# SCH_USB-Hub-with-audio-card_2025-04-09.net
KiCad netlist of a schematic drawn in EasyEDA
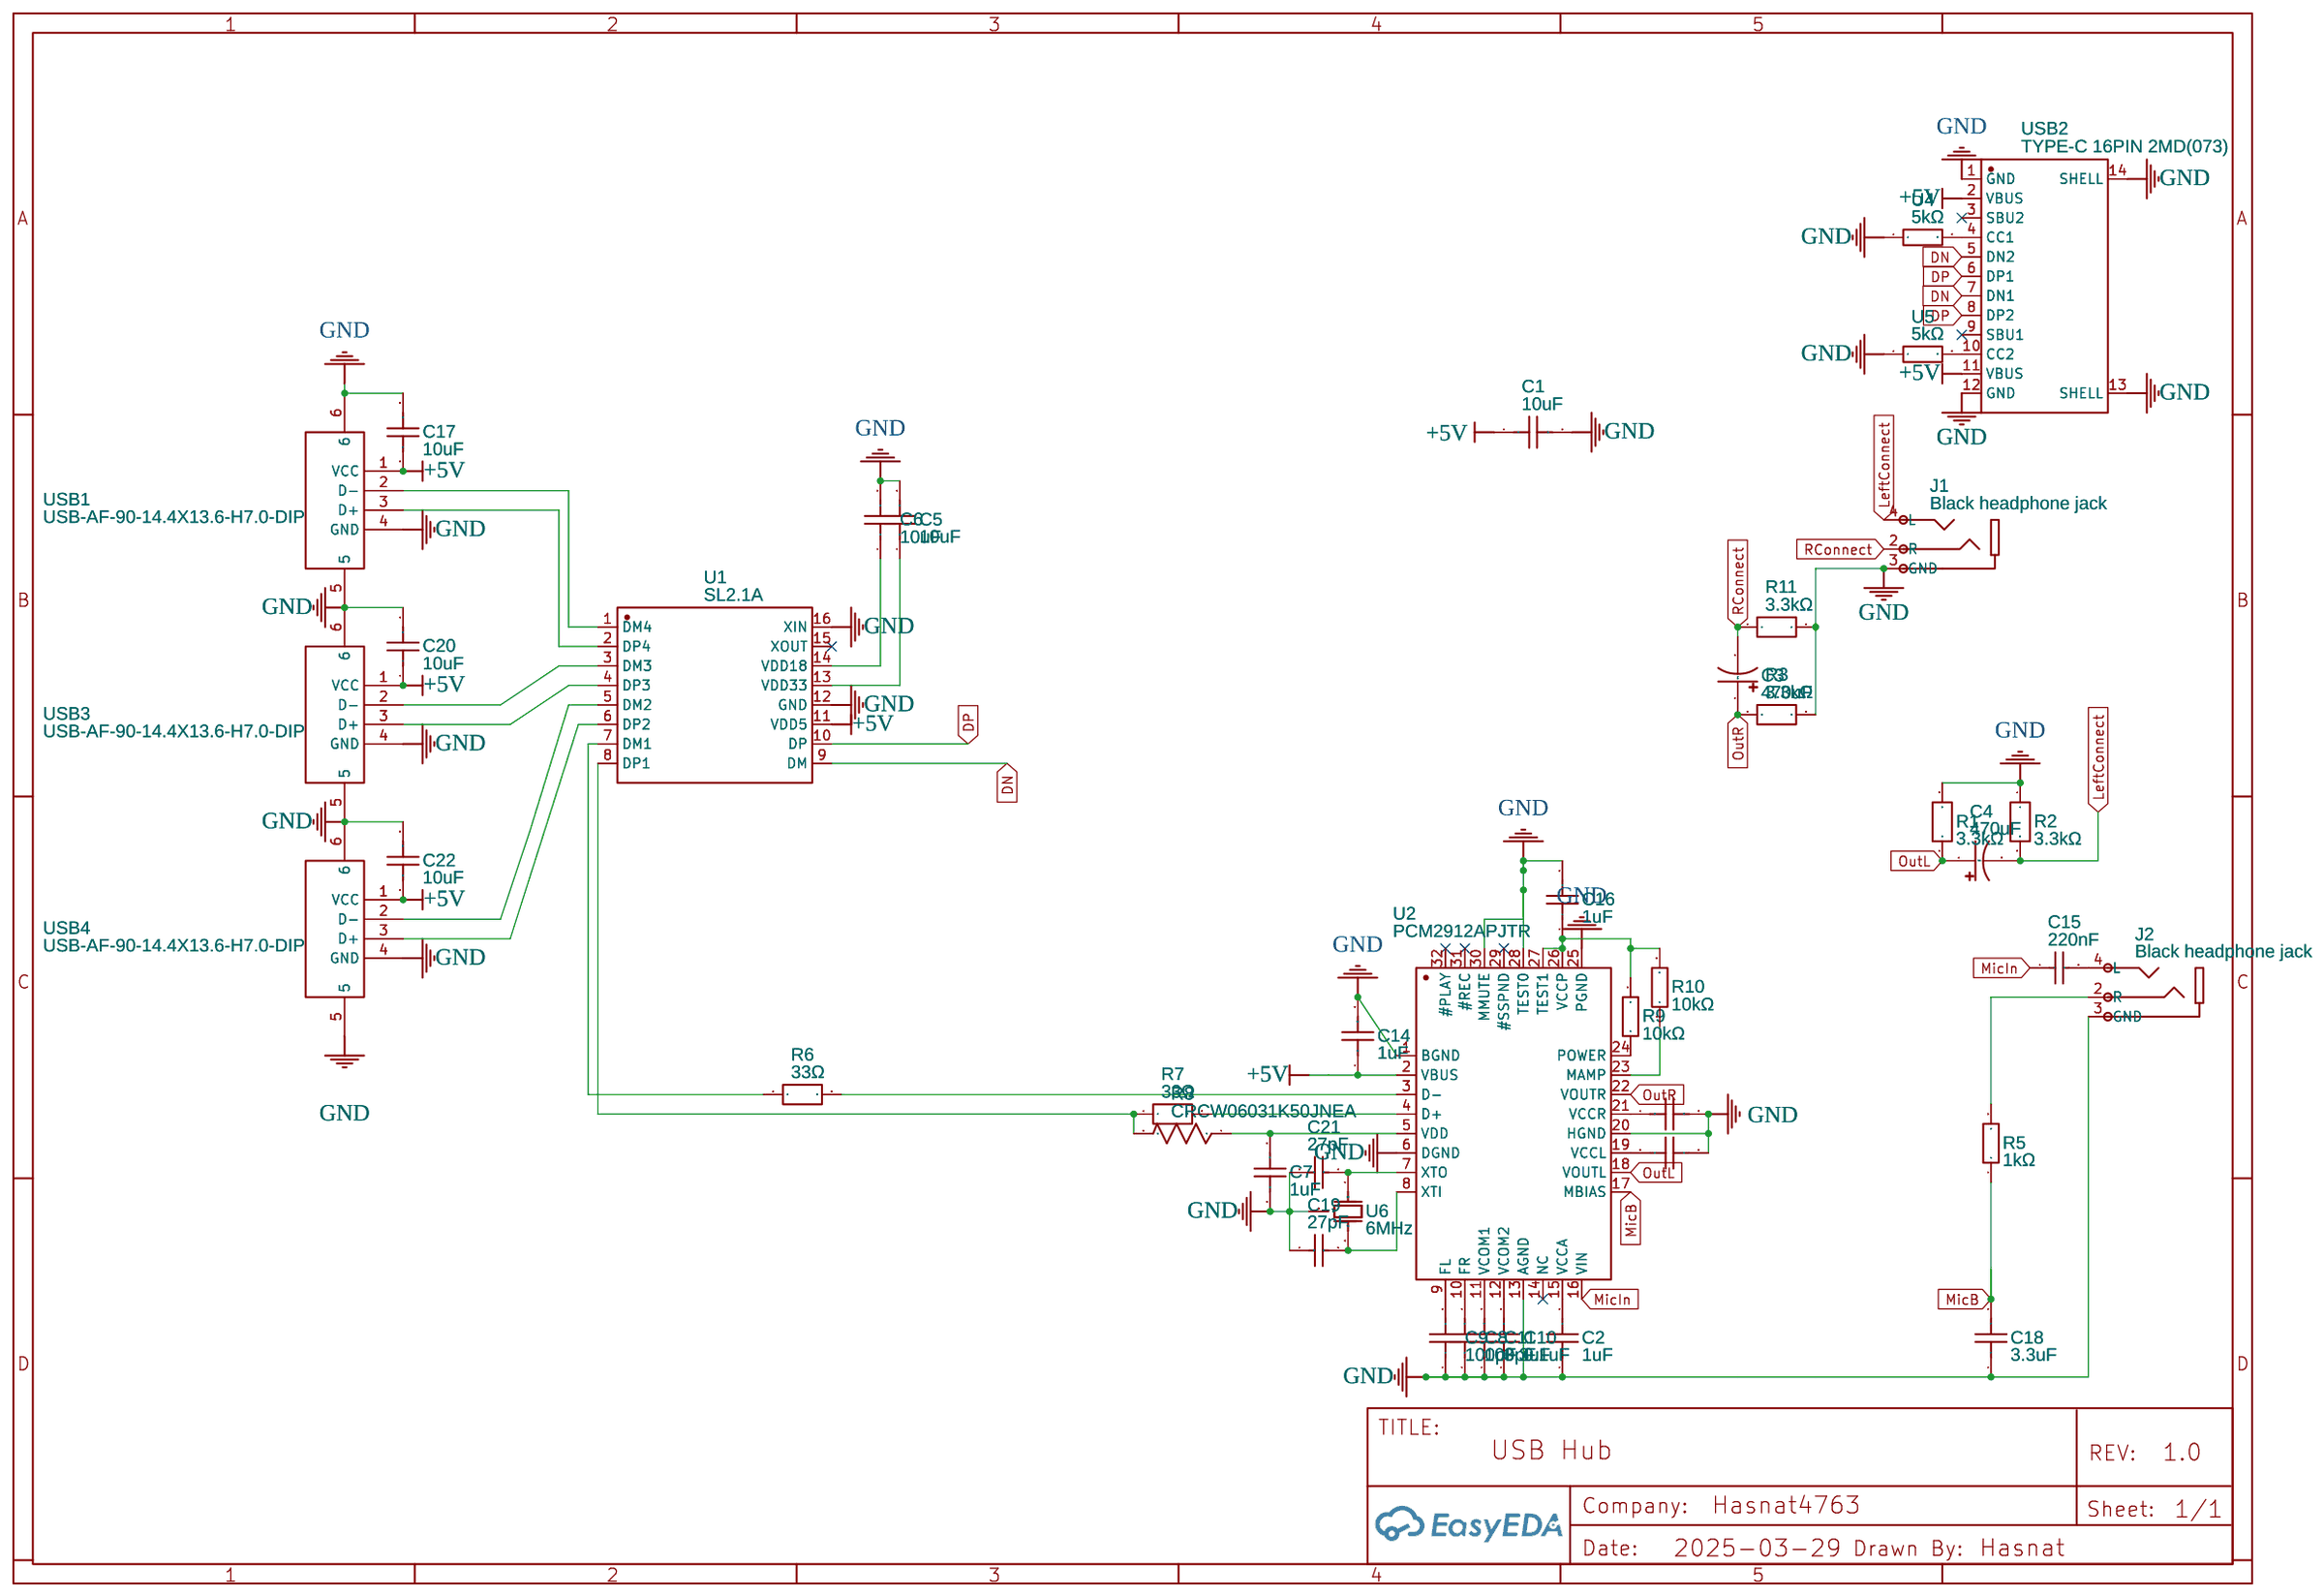
[diagram p0: schematic sheet]

(export (version "E")
  (design (tool "Eeschema 10.0.6"))
  (components
    (comp (ref "C1")
      (value "10uF")
      (fields
        (field (name "Manufacturer Part") "CL10A106KP8NNNC")
        (field (name "Manufacturer") "SAMSUNG(三星)")
      )
      (libsource (lib "") (part "CL10A106KP8NNNC_1"))
    )
    (comp (ref "C2")
      (value "1uF")
      (fields (field (name "Manufacturer Part") "CGB3B1X7R1A105K055AC") (field (name "Manufacturer") "TDK"))
      (libsource (lib "") (part "CGB3B1X7R1A105K055AC"))
    )
    (comp (ref "C3")
      (value "470uF")
      (fields (field (name "Manufacturer Part") "UKW1C471MPD") (field (name "Manufacturer") "Nichicon(尼吉康)"))
      (libsource (lib "") (part "UKW1C471MPD_1"))
    )
    (comp (ref "C4")
      (value "470uF")
      (fields (field (name "Manufacturer Part") "UKW1C471MPD") (field (name "Manufacturer") "Nichicon(尼吉康)"))
      (libsource (lib "") (part "UKW1C471MPD"))
    )
    (comp (ref "C5")
      (value "10uF")
      (fields
        (field (name "Manufacturer Part") "CL10A106KP8NNNC")
        (field (name "Manufacturer") "SAMSUNG(三星)")
      )
      (libsource (lib "") (part "CL10A106KP8NNNC"))
    )
    (comp (ref "C6")
      (value "10uF")
      (fields
        (field (name "Manufacturer Part") "CL10A106KP8NNNC")
        (field (name "Manufacturer") "SAMSUNG(三星)")
      )
      (libsource (lib "") (part "CL10A106KP8NNNC"))
    )
    (comp (ref "C7")
      (value "1uF")
      (fields
        (field (name "Manufacturer Part") "CL31B105KBHNNNE")
        (field (name "Manufacturer") "SAMSUNG(三星)")
      )
      (libsource (lib "") (part "CL31B105KBHNNNE_1"))
    )
    (comp (ref "C8")
      (value "100pF")
      (fields
        (field (name "Manufacturer Part") "CL10A106KP8NNNC")
        (field (name "Manufacturer") "SAMSUNG(三星)")
      )
      (libsource (lib "") (part "CL10A106KP8NNNC"))
    )
    (comp (ref "C9")
      (value "100pF")
      (fields
        (field (name "Manufacturer Part") "CL10A106KP8NNNC")
        (field (name "Manufacturer") "SAMSUNG(三星)")
      )
      (libsource (lib "") (part "CL10A106KP8NNNC"))
    )
    (comp (ref "C10")
      (value "0.1uF")
      (fields
        (field (name "Manufacturer Part") "CL10A106KP8NNNC")
        (field (name "Manufacturer") "SAMSUNG(三星)")
      )
      (libsource (lib "") (part "CL10A106KP8NNNC"))
    )
    (comp (ref "C11")
      (value "3.3uF")
      (fields
        (field (name "Manufacturer Part") "CL10A106KP8NNNC")
        (field (name "Manufacturer") "SAMSUNG(三星)")
      )
      (libsource (lib "") (part "CL10A106KP8NNNC"))
    )
    (comp (ref "C12")
      (value "1uF")
      (fields
        (field (name "Manufacturer Part") "CL31B105KBHNNNE")
        (field (name "Manufacturer") "SAMSUNG(三星)")
      )
      (libsource (lib "") (part "CL31B105KBHNNNE"))
    )
    (comp (ref "C13")
      (value "1uF")
      (fields
        (field (name "Manufacturer Part") "CL31B105KBHNNNE")
        (field (name "Manufacturer") "SAMSUNG(三星)")
      )
      (libsource (lib "") (part "CL31B105KBHNNNE"))
    )
    (comp (ref "C14")
      (value "1uF")
      (fields (field (name "Manufacturer Part") "CGB3B1X7R1A105K055AC") (field (name "Manufacturer") "TDK"))
      (libsource (lib "") (part "CGB3B1X7R1A105K055AC"))
    )
    (comp (ref "C15")
      (value "220nF")
      (fields
        (field (name "Manufacturer Part") "CL05A224KA5NNNC")
        (field (name "Manufacturer") "SAMSUNG(三星)")
      )
      (libsource (lib "") (part "CL05A224KA5NNNC"))
    )
    (comp (ref "C16")
      (value "1uF")
      (fields
        (field (name "Manufacturer Part") "CL31B105KBHNNNE")
        (field (name "Manufacturer") "SAMSUNG(三星)")
      )
      (libsource (lib "") (part "CL31B105KBHNNNE_1"))
    )
    (comp (ref "C17")
      (value "10uF")
      (fields
        (field (name "Manufacturer Part") "CL10A106KP8NNNC")
        (field (name "Manufacturer") "SAMSUNG(三星)")
      )
      (libsource (lib "") (part "CL10A106KP8NNNC"))
    )
    (comp (ref "C18")
      (value "3.3uF")
      (fields
        (field (name "Manufacturer Part") "KVD500L335M55A0T00")
        (field (name "Manufacturer") "NCC(日本贵弥功)")
      )
      (libsource (lib "") (part "KVD500L335M55A0T00"))
    )
    (comp (ref "C19")
      (value "27pF")
      (fields
        (field (name "Manufacturer Part") "CC0805JRNPO9BN270")
        (field (name "Manufacturer") "YAGEO(国巨)")
      )
      (libsource (lib "") (part "CC0805JRNPO9BN270"))
    )
    (comp (ref "C20")
      (value "10uF")
      (fields
        (field (name "Manufacturer Part") "CL10A106KP8NNNC")
        (field (name "Manufacturer") "SAMSUNG(三星)")
      )
      (libsource (lib "") (part "CL10A106KP8NNNC"))
    )
    (comp (ref "C21")
      (value "27pF")
      (fields
        (field (name "Manufacturer Part") "CC0805JRNPO9BN270")
        (field (name "Manufacturer") "YAGEO(国巨)")
      )
      (libsource (lib "") (part "CC0805JRNPO9BN270"))
    )
    (comp (ref "C22")
      (value "10uF")
      (fields
        (field (name "Manufacturer Part") "CL10A106KP8NNNC")
        (field (name "Manufacturer") "SAMSUNG(三星)")
      )
      (libsource (lib "") (part "CL10A106KP8NNNC"))
    )
    (comp (ref "J1")
      (value "Black headphone jack")
      (fields (field (name "Manufacturer Part") "320B直插") (field (name "Manufacturer") "BOOMELE(博穆精密)"))
      (libsource (lib "") (part "Black headphone jack"))
    )
    (comp (ref "J2")
      (value "Black headphone jack")
      (fields (field (name "Manufacturer Part") "320B直插") (field (name "Manufacturer") "BOOMELE(博穆精密)"))
      (libsource (lib "") (part "Black headphone jack"))
    )
    (comp (ref "R1")
      (value "3.3kΩ")
      (fields (field (name "Manufacturer Part") "CR-05JL7---3K3") (field (name "Manufacturer") "Viking(光颉)"))
      (libsource (lib "") (part "CR-05JL7---3K3_2"))
    )
    (comp (ref "R2")
      (value "3.3kΩ")
      (fields (field (name "Manufacturer Part") "CR-05JL7---3K3") (field (name "Manufacturer") "Viking(光颉)"))
      (libsource (lib "") (part "CR-05JL7---3K3"))
    )
    (comp (ref "R3")
      (value "3.3kΩ")
      (fields (field (name "Manufacturer Part") "CR-05JL7---3K3") (field (name "Manufacturer") "Viking(光颉)"))
      (libsource (lib "") (part "CR-05JL7---3K3_1"))
    )
    (comp (ref "R5")
      (value "1kΩ")
      (fields (field (name "Manufacturer Part") "RT0603DRD071KL") (field (name "Manufacturer") "YAGEO(国巨)"))
      (libsource (lib "") (part "RT0603DRD071KL"))
    )
    (comp (ref "R6")
      (value "33Ω")
      (fields
        (field (name "Manufacturer Part") "CRCW060333R0JNEA")
        (field (name "Manufacturer") "VISHAY(威世)")
      )
      (libsource (lib "") (part "CRCW060333R0JNEA"))
    )
    (comp (ref "R7")
      (value "33Ω")
      (fields
        (field (name "Manufacturer Part") "CRCW060333R0JNEA")
        (field (name "Manufacturer") "VISHAY(威世)")
      )
      (libsource (lib "") (part "CRCW060333R0JNEA"))
    )
    (comp (ref "R8") (value "CRCW06031K50JNEA") (libsource (lib "") (part "CRCW06031K50JNEA")))
    (comp (ref "R9")
      (value "10kΩ")
      (fields
        (field (name "Manufacturer Part") "CRCW060310K0JNEA")
        (field (name "Manufacturer") "VISHAY(威世)")
      )
      (libsource (lib "") (part "CRCW060310K0JNEA"))
    )
    (comp (ref "R10")
      (value "10kΩ")
      (fields
        (field (name "Manufacturer Part") "CRCW060310K0JNEA")
        (field (name "Manufacturer") "VISHAY(威世)")
      )
      (libsource (lib "") (part "CRCW060310K0JNEA"))
    )
    (comp (ref "R11")
      (value "3.3kΩ")
      (fields (field (name "Manufacturer Part") "CR-05JL7---3K3") (field (name "Manufacturer") "Viking(光颉)"))
      (libsource (lib "") (part "CR-05JL7---3K3_1"))
    )
    (comp (ref "U1")
      (value "SL2.1A")
      (fields (field (name "Manufacturer") "CoreChips(和芯润德)"))
      (libsource (lib "") (part "SL2.1A"))
    )
    (comp (ref "U2")
      (value "PCM2912APJTR")
      (fields (field (name "Manufacturer") "TI(德州仪器)"))
      (libsource (lib "") (part "PCM2912APJTR"))
    )
    (comp (ref "U4")
      (value "5kΩ")
      (fields (field (name "Manufacturer Part") "MFP1WSBRD52-5K") (field (name "Manufacturer") "YAGEO(国巨)"))
      (libsource (lib "") (part "MFP1WSBRD52-5K"))
    )
    (comp (ref "U5")
      (value "5kΩ")
      (fields (field (name "Manufacturer Part") "MFP1WSBRD52-5K") (field (name "Manufacturer") "YAGEO(国巨)"))
      (libsource (lib "") (part "MFP1WSBRD52-5K"))
    )
    (comp (ref "U6")
      (value "6MHz")
      (fields (field (name "Manufacturer Part") "ECS-60-18-5G3X-JGN-TR") (field (name "Manufacturer") "ECS"))
      (libsource (lib "") (part "ECS-60-18-5G3X-JGN-TR"))
    )
    (comp (ref "USB1")
      (value "USB-AF-90-14.4X13.6-H7.0-DIP")
      (fields (field (name "Manufacturer Part") "903-131A1011D10100") (field (name "Manufacturer") "精拓金"))
      (libsource (lib "") (part "USB-AF-90-14.4X13.6-H7.0-DIP"))
    )
    (comp (ref "USB2")
      (value "TYPE-C 16PIN 2MD(073)")
      (fields (field (name "Manufacturer") "SHOU HAN(首韩)"))
      (libsource (lib "") (part "TYPE-C 16PIN 2MD(073)"))
    )
    (comp (ref "USB3")
      (value "USB-AF-90-14.4X13.6-H7.0-DIP")
      (fields (field (name "Manufacturer Part") "903-131A1011D10100") (field (name "Manufacturer") "精拓金"))
      (libsource (lib "") (part "USB-AF-90-14.4X13.6-H7.0-DIP"))
    )
    (comp (ref "USB4")
      (value "USB-AF-90-14.4X13.6-H7.0-DIP")
      (fields (field (name "Manufacturer Part") "903-131A1011D10100") (field (name "Manufacturer") "精拓金"))
      (libsource (lib "") (part "USB-AF-90-14.4X13.6-H7.0-DIP"))
    )
  )
  (nets
    (net (code "1") (name "+5V") (class "Default")
      (node (ref "C1") (pin "1") (pinfunction "1_1") (pintype "unspecified"))
      (node (ref "C14") (pin "1") (pinfunction "1_1") (pintype "unspecified"))
      (node (ref "C17") (pin "1") (pinfunction "1_1") (pintype "unspecified"))
      (node (ref "C20") (pin "1") (pinfunction "1_1") (pintype "unspecified"))
      (node (ref "C22") (pin "1") (pinfunction "1_1") (pintype "unspecified"))
      (node (ref "U1") (pin "11") (pinfunction "VDD5_11") (pintype "unspecified"))
      (node (ref "U2") (pin "2") (pinfunction "VBUS_2") (pintype "unspecified"))
      (node (ref "USB1") (pin "1") (pinfunction "VCC_1") (pintype "unspecified"))
      (node (ref "USB2") (pin "11") (pinfunction "VBUS_11") (pintype "unspecified"))
      (node (ref "USB2") (pin "2") (pinfunction "VBUS_2") (pintype "unspecified"))
      (node (ref "USB3") (pin "1") (pinfunction "VCC_1") (pintype "unspecified"))
      (node (ref "USB4") (pin "1") (pinfunction "VCC_1") (pintype "unspecified"))
    )
    (net (code "2") (name "DN") (class "Default")
      (node (ref "U1") (pin "9") (pinfunction "DM_9") (pintype "unspecified"))
      (node (ref "USB2") (pin "5") (pinfunction "DN2_5") (pintype "unspecified"))
      (node (ref "USB2") (pin "7") (pinfunction "DN1_7") (pintype "unspecified"))
    )
    (net (code "3") (name "DP") (class "Default")
      (node (ref "U1") (pin "10") (pinfunction "DP_10") (pintype "unspecified"))
      (node (ref "USB2") (pin "6") (pinfunction "DP1_6") (pintype "unspecified"))
      (node (ref "USB2") (pin "8") (pinfunction "DP2_8") (pintype "unspecified"))
    )
    (net (code "4") (name "GND") (class "Default")
      (node (ref "C1") (pin "2") (pinfunction "2_2") (pintype "unspecified"))
      (node (ref "C10") (pin "1") (pinfunction "1_1") (pintype "unspecified"))
      (node (ref "C11") (pin "1") (pinfunction "1_1") (pintype "unspecified"))
      (node (ref "C12") (pin "2") (pinfunction "2_2") (pintype "unspecified"))
      (node (ref "C13") (pin "2") (pinfunction "2_2") (pintype "unspecified"))
      (node (ref "C14") (pin "2") (pinfunction "2_2") (pintype "unspecified"))
      (node (ref "C16") (pin "2") (pinfunction "2_2") (pintype "unspecified"))
      (node (ref "C17") (pin "2") (pinfunction "2_2") (pintype "unspecified"))
      (node (ref "C18") (pin "1") (pinfunction "1_1") (pintype "unspecified"))
      (node (ref "C19") (pin "1") (pinfunction "1_1") (pintype "input"))
      (node (ref "C2") (pin "1") (pinfunction "1_1") (pintype "unspecified"))
      (node (ref "C20") (pin "2") (pinfunction "2_2") (pintype "unspecified"))
      (node (ref "C21") (pin "1") (pinfunction "1_1") (pintype "input"))
      (node (ref "C22") (pin "2") (pinfunction "2_2") (pintype "unspecified"))
      (node (ref "C5") (pin "2") (pinfunction "2_2") (pintype "unspecified"))
      (node (ref "C6") (pin "2") (pinfunction "2_2") (pintype "unspecified"))
      (node (ref "C7") (pin "1") (pinfunction "1_1") (pintype "unspecified"))
      (node (ref "C8") (pin "1") (pinfunction "1_1") (pintype "unspecified"))
      (node (ref "C9") (pin "1") (pinfunction "1_1") (pintype "unspecified"))
      (node (ref "J1") (pin "3") (pinfunction "GND_3") (pintype "input"))
      (node (ref "J2") (pin "3") (pinfunction "GND_3") (pintype "input"))
      (node (ref "R1") (pin "2") (pinfunction "2_2") (pintype "unspecified"))
      (node (ref "R11") (pin "2") (pinfunction "2_2") (pintype "unspecified"))
      (node (ref "R2") (pin "1") (pinfunction "1_1") (pintype "unspecified"))
      (node (ref "R3") (pin "2") (pinfunction "2_2") (pintype "unspecified"))
      (node (ref "U1") (pin "12") (pinfunction "GND_12") (pintype "unspecified"))
      (node (ref "U1") (pin "16") (pinfunction "XIN_16") (pintype "unspecified"))
      (node (ref "U2") (pin "1") (pinfunction "BGND_1") (pintype "unspecified"))
      (node (ref "U2") (pin "13") (pinfunction "AGND_13") (pintype "unspecified"))
      (node (ref "U2") (pin "20") (pinfunction "HGND_20") (pintype "unspecified"))
      (node (ref "U2") (pin "25") (pinfunction "PGND_25") (pintype "unspecified"))
      (node (ref "U2") (pin "28") (pinfunction "TEST0_28") (pintype "unspecified"))
      (node (ref "U2") (pin "30") (pinfunction "MMUTE_30") (pintype "unspecified"))
      (node (ref "U2") (pin "6") (pinfunction "DGND_6") (pintype "unspecified"))
      (node (ref "U4") (pin "1") (pinfunction "1_1") (pintype "unspecified"))
      (node (ref "U5") (pin "1") (pinfunction "1_1") (pintype "unspecified"))
      (node (ref "U6") (pin "3") (pinfunction "GND_3") (pintype "input"))
      (node (ref "USB1") (pin "4") (pinfunction "GND_4") (pintype "unspecified"))
      (node (ref "USB1") (pin "5") (pinfunction "5_5") (pintype "unspecified"))
      (node (ref "USB1") (pin "6") (pinfunction "6_6") (pintype "unspecified"))
      (node (ref "USB2") (pin "1") (pinfunction "GND_1") (pintype "unspecified"))
      (node (ref "USB2") (pin "12") (pinfunction "GND_12") (pintype "unspecified"))
      (node (ref "USB2") (pin "13") (pinfunction "SHELL_13") (pintype "unspecified"))
      (node (ref "USB2") (pin "14") (pinfunction "SHELL_14") (pintype "unspecified"))
      (node (ref "USB3") (pin "4") (pinfunction "GND_4") (pintype "unspecified"))
      (node (ref "USB3") (pin "5") (pinfunction "5_5") (pintype "unspecified"))
      (node (ref "USB3") (pin "6") (pinfunction "6_6") (pintype "unspecified"))
      (node (ref "USB4") (pin "4") (pinfunction "GND_4") (pintype "unspecified"))
      (node (ref "USB4") (pin "5") (pinfunction "5_5") (pintype "unspecified"))
      (node (ref "USB4") (pin "6") (pinfunction "6_6") (pintype "unspecified"))
    )
    (net (code "5") (name "LeftConnect") (class "Default")
      (node (ref "C4") (pin "2") (pinfunction "2_2") (pintype "unspecified"))
      (node (ref "J1") (pin "4") (pinfunction "L_4") (pintype "input"))
      (node (ref "R2") (pin "2") (pinfunction "2_2") (pintype "unspecified"))
    )
    (net (code "6") (name "MicB") (class "Default")
      (node (ref "C18") (pin "2") (pinfunction "2_2") (pintype "unspecified"))
      (node (ref "R5") (pin "1") (pinfunction "1_1") (pintype "unspecified"))
      (node (ref "U2") (pin "17") (pinfunction "MBIAS_17") (pintype "unspecified"))
    )
    (net (code "7") (name "MicIn") (class "Default")
      (node (ref "C15") (pin "1") (pinfunction "1_1") (pintype "input"))
      (node (ref "U2") (pin "16") (pinfunction "VIN_16") (pintype "unspecified"))
    )
    (net (code "8") (name "Net-(J2-L)") (class "Default")
      (node (ref "C15") (pin "2") (pinfunction "2_2") (pintype "input"))
      (node (ref "J2") (pin "4") (pinfunction "L_4") (pintype "input"))
    )
    (net (code "9") (name "Net-(J2-R)") (class "Default")
      (node (ref "J2") (pin "2") (pinfunction "R_2") (pintype "input"))
      (node (ref "R5") (pin "2") (pinfunction "2_2") (pintype "unspecified"))
    )
    (net (code "10") (name "Net-(U1-DM1)") (class "Default")
      (node (ref "R6") (pin "1") (pinfunction "1_1") (pintype "unspecified"))
      (node (ref "U1") (pin "7") (pinfunction "DM1_7") (pintype "unspecified"))
    )
    (net (code "11") (name "Net-(U1-DM2)") (class "Default")
      (node (ref "U1") (pin "5") (pinfunction "DM2_5") (pintype "unspecified"))
      (node (ref "USB4") (pin "2") (pinfunction "D-_2") (pintype "unspecified"))
    )
    (net (code "12") (name "Net-(U1-DM3)") (class "Default")
      (node (ref "U1") (pin "3") (pinfunction "DM3_3") (pintype "unspecified"))
      (node (ref "USB3") (pin "2") (pinfunction "D-_2") (pintype "unspecified"))
    )
    (net (code "13") (name "Net-(U1-DM4)") (class "Default")
      (node (ref "U1") (pin "1") (pinfunction "DM4_1") (pintype "unspecified"))
      (node (ref "USB1") (pin "2") (pinfunction "D-_2") (pintype "unspecified"))
    )
    (net (code "14") (name "Net-(U1-DP1)") (class "Default")
      (node (ref "R7") (pin "1") (pinfunction "1_1") (pintype "unspecified"))
      (node (ref "R8") (pin "2") (pinfunction "2_2") (pintype "unspecified"))
      (node (ref "U1") (pin "8") (pinfunction "DP1_8") (pintype "unspecified"))
    )
    (net (code "15") (name "Net-(U1-DP2)") (class "Default")
      (node (ref "U1") (pin "6") (pinfunction "DP2_6") (pintype "unspecified"))
      (node (ref "USB4") (pin "3") (pinfunction "D+_3") (pintype "unspecified"))
    )
    (net (code "16") (name "Net-(U1-DP3)") (class "Default")
      (node (ref "U1") (pin "4") (pinfunction "DP3_4") (pintype "unspecified"))
      (node (ref "USB3") (pin "3") (pinfunction "D+_3") (pintype "unspecified"))
    )
    (net (code "17") (name "Net-(U1-DP4)") (class "Default")
      (node (ref "U1") (pin "2") (pinfunction "DP4_2") (pintype "unspecified"))
      (node (ref "USB1") (pin "3") (pinfunction "D+_3") (pintype "unspecified"))
    )
    (net (code "18") (name "Net-(U1-VDD18)") (class "Default")
      (node (ref "C6") (pin "1") (pinfunction "1_1") (pintype "unspecified"))
      (node (ref "U1") (pin "14") (pinfunction "VDD18_14") (pintype "unspecified"))
    )
    (net (code "19") (name "Net-(U1-VDD33)") (class "Default")
      (node (ref "C5") (pin "1") (pinfunction "1_1") (pintype "unspecified"))
      (node (ref "U1") (pin "13") (pinfunction "VDD33_13") (pintype "unspecified"))
    )
    (net (code "20") (name "Net-(U2-D+)") (class "Default")
      (node (ref "R7") (pin "2") (pinfunction "2_2") (pintype "unspecified"))
      (node (ref "U2") (pin "4") (pinfunction "D+_4") (pintype "unspecified"))
    )
    (net (code "21") (name "Net-(U2-D-)") (class "Default")
      (node (ref "R6") (pin "2") (pinfunction "2_2") (pintype "unspecified"))
      (node (ref "U2") (pin "3") (pinfunction "D-_3") (pintype "unspecified"))
    )
    (net (code "22") (name "Net-(U2-FL)") (class "Default")
      (node (ref "C9") (pin "2") (pinfunction "2_2") (pintype "unspecified"))
      (node (ref "U2") (pin "9") (pinfunction "FL_9") (pintype "unspecified"))
    )
    (net (code "23") (name "Net-(U2-FR)") (class "Default")
      (node (ref "C8") (pin "2") (pinfunction "2_2") (pintype "unspecified"))
      (node (ref "U2") (pin "10") (pinfunction "FR_10") (pintype "unspecified"))
    )
    (net (code "24") (name "Net-(U2-MAMP)") (class "Default")
      (node (ref "R10") (pin "1") (pinfunction "1_1") (pintype "unspecified"))
      (node (ref "U2") (pin "23") (pinfunction "MAMP_23") (pintype "unspecified"))
    )
    (net (code "25") (name "Net-(U2-POWER)") (class "Default")
      (node (ref "R9") (pin "1") (pinfunction "1_1") (pintype "unspecified"))
      (node (ref "U2") (pin "24") (pinfunction "POWER_24") (pintype "unspecified"))
    )
    (net (code "26") (name "Net-(U2-TEST1)") (class "Default")
      (node (ref "C16") (pin "1") (pinfunction "1_1") (pintype "unspecified"))
      (node (ref "R10") (pin "2") (pinfunction "2_2") (pintype "unspecified"))
      (node (ref "R9") (pin "2") (pinfunction "2_2") (pintype "unspecified"))
      (node (ref "U2") (pin "26") (pinfunction "VCCP_26") (pintype "unspecified"))
      (node (ref "U2") (pin "27") (pinfunction "TEST1_27") (pintype "unspecified"))
    )
    (net (code "27") (name "Net-(U2-VCCA)") (class "Default")
      (node (ref "C2") (pin "2") (pinfunction "2_2") (pintype "unspecified"))
      (node (ref "U2") (pin "15") (pinfunction "VCCA_15") (pintype "unspecified"))
    )
    (net (code "28") (name "Net-(U2-VCCL)") (class "Default")
      (node (ref "C13") (pin "1") (pinfunction "1_1") (pintype "unspecified"))
      (node (ref "U2") (pin "19") (pinfunction "VCCL_19") (pintype "unspecified"))
    )
    (net (code "29") (name "Net-(U2-VCCR)") (class "Default")
      (node (ref "C12") (pin "1") (pinfunction "1_1") (pintype "unspecified"))
      (node (ref "U2") (pin "21") (pinfunction "VCCR_21") (pintype "unspecified"))
    )
    (net (code "30") (name "Net-(U2-VCOM1)") (class "Default")
      (node (ref "C11") (pin "2") (pinfunction "2_2") (pintype "unspecified"))
      (node (ref "U2") (pin "11") (pinfunction "VCOM1_11") (pintype "unspecified"))
    )
    (net (code "31") (name "Net-(U2-VCOM2)") (class "Default")
      (node (ref "C10") (pin "2") (pinfunction "2_2") (pintype "unspecified"))
      (node (ref "U2") (pin "12") (pinfunction "VCOM2_12") (pintype "unspecified"))
    )
    (net (code "32") (name "Net-(U2-VDD)") (class "Default")
      (node (ref "C7") (pin "2") (pinfunction "2_2") (pintype "unspecified"))
      (node (ref "R8") (pin "1") (pinfunction "1_1") (pintype "unspecified"))
      (node (ref "U2") (pin "5") (pinfunction "VDD_5") (pintype "unspecified"))
    )
    (net (code "33") (name "Net-(U2-XTI)") (class "Default")
      (node (ref "C19") (pin "2") (pinfunction "2_2") (pintype "input"))
      (node (ref "U2") (pin "8") (pinfunction "XTI_8") (pintype "unspecified"))
      (node (ref "U6") (pin "2") (pinfunction "Out/In_2") (pintype "input"))
    )
    (net (code "34") (name "Net-(U2-XTO)") (class "Default")
      (node (ref "C21") (pin "2") (pinfunction "2_2") (pintype "input"))
      (node (ref "U2") (pin "7") (pinfunction "XTO_7") (pintype "unspecified"))
      (node (ref "U6") (pin "1") (pinfunction "In/Out_1") (pintype "input"))
    )
    (net (code "35") (name "Net-(USB2-CC1)") (class "Default")
      (node (ref "U4") (pin "2") (pinfunction "2_2") (pintype "unspecified"))
      (node (ref "USB2") (pin "4") (pinfunction "CC1_4") (pintype "unspecified"))
    )
    (net (code "36") (name "Net-(USB2-CC2)") (class "Default")
      (node (ref "U5") (pin "2") (pinfunction "2_2") (pintype "unspecified"))
      (node (ref "USB2") (pin "10") (pinfunction "CC2_10") (pintype "unspecified"))
    )
    (net (code "37") (name "OutL") (class "Default")
      (node (ref "C4") (pin "1") (pinfunction "1_1") (pintype "unspecified"))
      (node (ref "R1") (pin "1") (pinfunction "1_1") (pintype "unspecified"))
      (node (ref "U2") (pin "18") (pinfunction "VOUTL_18") (pintype "unspecified"))
    )
    (net (code "38") (name "OutR") (class "Default")
      (node (ref "C3") (pin "1") (pinfunction "1_1") (pintype "unspecified"))
      (node (ref "R3") (pin "1") (pinfunction "1_1") (pintype "unspecified"))
      (node (ref "U2") (pin "22") (pinfunction "VOUTR_22") (pintype "unspecified"))
    )
    (net (code "39") (name "RConnect") (class "Default")
      (node (ref "C3") (pin "2") (pinfunction "2_2") (pintype "unspecified"))
      (node (ref "J1") (pin "2") (pinfunction "R_2") (pintype "input"))
      (node (ref "R11") (pin "1") (pinfunction "1_1") (pintype "unspecified"))
    )
    (net (code "40") (name "unconnected-(U1-XOUT-Pad15)") (class "Default")
      (node (ref "U1") (pin "15") (pinfunction "XOUT_15") (pintype "unspecified+no_connect"))
    )
    (net (code "41") (name "unconnected-(U2-#PLAY-Pad32)") (class "Default")
      (node (ref "U2") (pin "32") (pinfunction "#PLAY_32") (pintype "unspecified+no_connect"))
    )
    (net (code "42") (name "unconnected-(U2-#REC-Pad31)") (class "Default")
      (node (ref "U2") (pin "31") (pinfunction "#REC_31") (pintype "unspecified+no_connect"))
    )
    (net (code "43") (name "unconnected-(U2-#SSPND-Pad29)") (class "Default")
      (node (ref "U2") (pin "29") (pinfunction "#SSPND_29") (pintype "unspecified+no_connect"))
    )
    (net (code "44") (name "unconnected-(U2-NC-Pad14)") (class "Default")
      (node (ref "U2") (pin "14") (pinfunction "NC_14") (pintype "unspecified+no_connect"))
    )
    (net (code "45") (name "unconnected-(USB2-SBU1-Pad9)") (class "Default")
      (node (ref "USB2") (pin "9") (pinfunction "SBU1_9") (pintype "unspecified+no_connect"))
    )
    (net (code "46") (name "unconnected-(USB2-SBU2-Pad3)") (class "Default")
      (node (ref "USB2") (pin "3") (pinfunction "SBU2_3") (pintype "unspecified+no_connect"))
    )
  )
)
